# testpcb.net
KiCad netlist of a schematic drawn in EasyEDA Pro
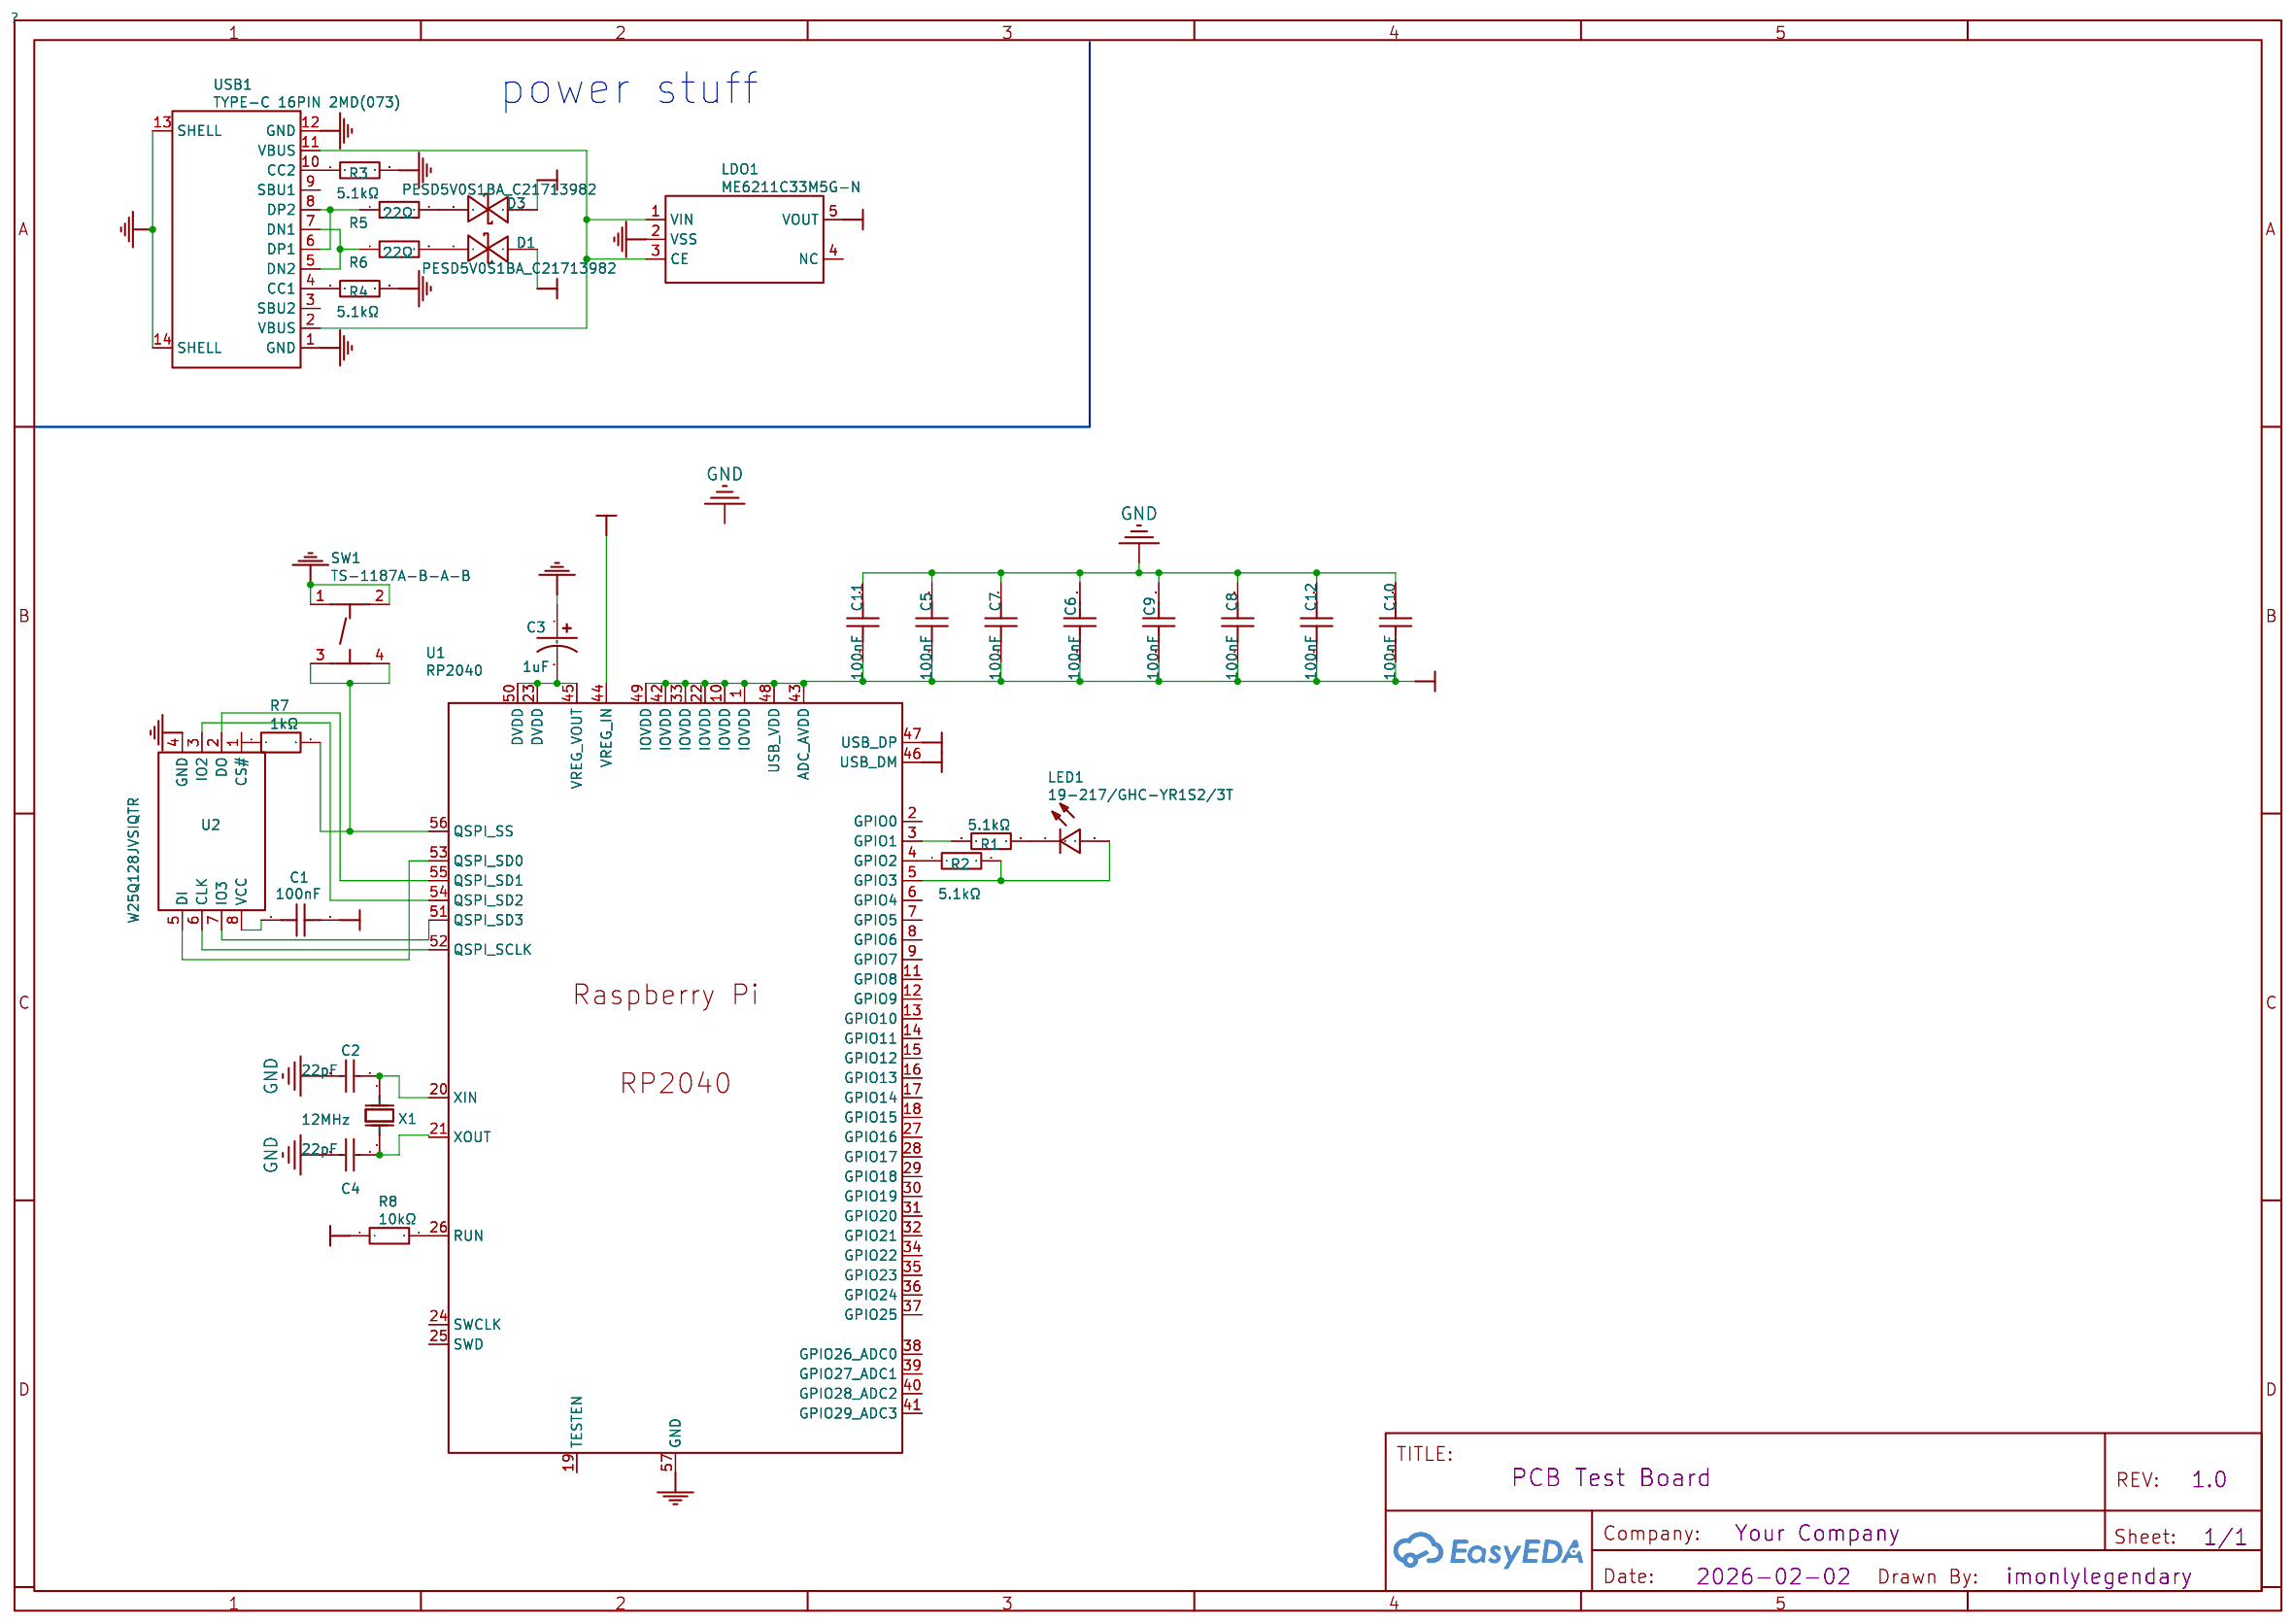
[diagram p0: schematic sheet]

(export (version "E")
  (design (tool "Eeschema 10.0.6"))
  (components
    (comp (ref "C1")
      (value "100nF")
      (footprint "easyedapro:C0402")
      (fields
        (field (name "Manufacturer Part") "CL05B104KB54PNC")
        (field (name "Manufacturer") "SAMSUNG(三星)")
        (field (name "Contributor") "LCSC")
      )
      (libsource (lib "") (part "100nF_1"))
    )
    (comp (ref "C2")
      (value "22pF")
      (footprint "easyedapro:C0603")
      (fields
        (field (name "Manufacturer Part") "CL10C220JB8NNNC")
        (field (name "Manufacturer") "SAMSUNG(三星)")
      )
      (libsource (lib "easyedapro") (part "22pF"))
    )
    (comp (ref "C3")
      (value "1uF")
      (footprint "easyedapro:CAP-TH_BD5.0-P2.00-D0.5-FD-1")
      (fields
        (field (name "Manufacturer Part") "50YXF1MEFC5X11")
        (field (name "Manufacturer") "rubycon(红宝石)")
        (field (name "Contributor") "lcsc")
      )
      (libsource (lib "easyedapro") (part "1uF"))
    )
    (comp (ref "C4")
      (value "22pF")
      (footprint "easyedapro:C0603")
      (fields
        (field (name "Manufacturer Part") "CL10C220JB8NNNC")
        (field (name "Manufacturer") "SAMSUNG(三星)")
      )
      (libsource (lib "easyedapro") (part "22pF"))
    )
    (comp (ref "C5")
      (value "100nF")
      (footprint "easyedapro:C0603")
      (fields
        (field (name "Manufacturer Part") "CC0603KRX7R9BB104")
        (field (name "Manufacturer") "YAGEO(国巨)")
      )
      (libsource (lib "easyedapro") (part "100nF"))
    )
    (comp (ref "C6")
      (value "100nF")
      (footprint "easyedapro:C0603")
      (fields
        (field (name "Manufacturer Part") "CC0603KRX7R9BB104")
        (field (name "Manufacturer") "YAGEO(国巨)")
      )
      (libsource (lib "easyedapro") (part "100nF"))
    )
    (comp (ref "C7")
      (value "100nF")
      (footprint "easyedapro:C0603")
      (fields
        (field (name "Manufacturer Part") "CC0603KRX7R9BB104")
        (field (name "Manufacturer") "YAGEO(国巨)")
      )
      (libsource (lib "easyedapro") (part "100nF"))
    )
    (comp (ref "C8")
      (value "100nF")
      (footprint "easyedapro:C0603")
      (fields
        (field (name "Manufacturer Part") "CC0603KRX7R9BB104")
        (field (name "Manufacturer") "YAGEO(国巨)")
      )
      (libsource (lib "easyedapro") (part "100nF"))
    )
    (comp (ref "C9")
      (value "100nF")
      (footprint "easyedapro:C0603")
      (fields
        (field (name "Manufacturer Part") "CC0603KRX7R9BB104")
        (field (name "Manufacturer") "YAGEO(国巨)")
      )
      (libsource (lib "easyedapro") (part "100nF"))
    )
    (comp (ref "C10")
      (value "100nF")
      (footprint "easyedapro:C0603")
      (fields
        (field (name "Manufacturer Part") "CC0603KRX7R9BB104")
        (field (name "Manufacturer") "YAGEO(国巨)")
      )
      (libsource (lib "easyedapro") (part "100nF"))
    )
    (comp (ref "C11")
      (value "100nF")
      (footprint "easyedapro:C0603")
      (fields
        (field (name "Manufacturer Part") "CC0603KRX7R9BB104")
        (field (name "Manufacturer") "YAGEO(国巨)")
      )
      (libsource (lib "easyedapro") (part "100nF"))
    )
    (comp (ref "C12")
      (value "100nF")
      (footprint "easyedapro:C0603")
      (fields
        (field (name "Manufacturer Part") "CC0603KRX7R9BB104")
        (field (name "Manufacturer") "YAGEO(国巨)")
      )
      (libsource (lib "easyedapro") (part "100nF"))
    )
    (comp (ref "D1")
      (value "PESD5V0S1BA_C21713982")
      (footprint "easyedapro:SOD-323_L1.7-W1.3-LS2.5-BI")
      (fields
        (field (name "Manufacturer Part") "PESD5V0S1BA")
        (field (name "Manufacturer") "GOODWORK(固得沃克)")
        (field (name "Contributor") "lcsc")
      )
      (libsource (lib "easyedapro") (part "PESD5V0S1BA_C21713982"))
    )
    (comp (ref "D3")
      (value "PESD5V0S1BA_C21713982")
      (footprint "easyedapro:SOD-323_L1.7-W1.3-LS2.5-BI")
      (fields
        (field (name "Manufacturer Part") "PESD5V0S1BA")
        (field (name "Manufacturer") "GOODWORK(固得沃克)")
        (field (name "Contributor") "lcsc")
      )
      (libsource (lib "easyedapro") (part "PESD5V0S1BA_C21713982"))
    )
    (comp (ref "LDO1")
      (value "ME6211C33M5G-N")
      (footprint "easyedapro:SOT-23-5_L3.0-W1.7-P0.95-LS2.8-BL")
      (fields (field (name "Manufacturer") "MICRONE(南京微盟)"))
      (libsource (lib "easyedapro") (part "ME6211C33M5G-N"))
    )
    (comp (ref "LED1")
      (value "19-217/GHC-YR1S2/3T")
      (footprint "easyedapro:LED0603-RD")
      (fields (field (name "Manufacturer") "EVERLIGHT(亿光)"))
      (libsource (lib "easyedapro") (part "19-217/GHC-YR1S2/3T"))
    )
    (comp (ref "R1")
      (value "5.1kΩ")
      (footprint "easyedapro:R0603")
      (fields
        (field (name "Manufacturer Part") "0603WAF5101T5E")
        (field (name "Manufacturer") "UNI-ROYAL(厚声)")
      )
      (libsource (lib "easyedapro") (part "5.1kΩ"))
    )
    (comp (ref "R2")
      (value "5.1kΩ")
      (footprint "easyedapro:R0603")
      (fields
        (field (name "Manufacturer Part") "0603WAF5101T5E")
        (field (name "Manufacturer") "UNI-ROYAL(厚声)")
      )
      (libsource (lib "easyedapro") (part "5.1kΩ"))
    )
    (comp (ref "R3")
      (value "5.1kΩ")
      (footprint "easyedapro:R0603")
      (fields
        (field (name "Manufacturer Part") "0603WAF5101T5E")
        (field (name "Manufacturer") "UNI-ROYAL(厚声)")
      )
      (libsource (lib "easyedapro") (part "5.1kΩ"))
    )
    (comp (ref "R4")
      (value "5.1kΩ")
      (footprint "easyedapro:R0603")
      (fields
        (field (name "Manufacturer Part") "0603WAF5101T5E")
        (field (name "Manufacturer") "UNI-ROYAL(厚声)")
      )
      (libsource (lib "easyedapro") (part "5.1kΩ"))
    )
    (comp (ref "R5")
      (value "22Ω")
      (footprint "easyedapro:R0603")
      (fields
        (field (name "Manufacturer Part") "0603WAF220JT5E")
        (field (name "Manufacturer") "UNI-ROYAL(厚声)")
      )
      (libsource (lib "easyedapro") (part "22Ω"))
    )
    (comp (ref "R6")
      (value "22Ω")
      (footprint "easyedapro:R0603")
      (fields
        (field (name "Manufacturer Part") "0603WAF220JT5E")
        (field (name "Manufacturer") "UNI-ROYAL(厚声)")
      )
      (libsource (lib "easyedapro") (part "22Ω"))
    )
    (comp (ref "R7")
      (value "1kΩ")
      (footprint "easyedapro:R0603")
      (fields
        (field (name "Manufacturer Part") "FRC0603F1001TS")
        (field (name "Manufacturer") "FOJAN(富捷)")
        (field (name "Contributor") "lcsc")
      )
      (libsource (lib "easyedapro") (part "1kΩ"))
    )
    (comp (ref "R8")
      (value "10kΩ")
      (footprint "easyedapro:R0603")
      (fields
        (field (name "Manufacturer Part") "0603WAF1002T5E")
        (field (name "Manufacturer") "UNI-ROYAL(厚声)")
      )
      (libsource (lib "easyedapro") (part "10kΩ"))
    )
    (comp (ref "SW1")
      (value "TS-1187A-B-A-B")
      (footprint "easyedapro:SW-SMD_4P-L5.1-W5.1-P3.70-LS6.5-TL_H1.5")
      (fields (field (name "Manufacturer") "XKB Connection(中国星坤)") (field (name "Contributor") "LCSC"))
      (libsource (lib "easyedapro") (part "TS-1187A-B-A-B"))
    )
    (comp (ref "U1")
      (value "RP2040")
      (footprint "easyedapro:LQFN-56_L7.0-W7.0-P0.4-EP")
      (fields (field (name "Manufacturer") "Raspberry Pi(树莓派)") (field (name "Contributor") "LCSC"))
      (libsource (lib "easyedapro") (part "RP2040"))
    )
    (comp (ref "U2")
      (value "W25Q128JVSIQTR")
      (footprint "easyedapro:SOIC-8_L5.3-W5.3-P1.27-LS8.0-BL")
      (fields (field (name "Manufacturer Part") "W25Q128JVSIQ") (field (name "Manufacturer") "Winbond(华邦)"))
      (libsource (lib "easyedapro") (part "W25Q128JVSIQTR"))
    )
    (comp (ref "USB1")
      (value "TYPE-C 16PIN 2MD(073)")
      (footprint "easyedapro:USB-C-SMD_TYPE-C-6PIN-2MD-073")
      (fields (field (name "Manufacturer") "SHOU HAN(首韩)") (field (name "Contributor") "LCSC"))
      (libsource (lib "easyedapro") (part "TYPE-C 16PIN 2MD(073)"))
    )
    (comp (ref "X1")
      (value "12MHz")
      (footprint "easyedapro:HC-49US_L11.5-W4.5-P4.88")
      (fields (field (name "Manufacturer Part") "X49SD12MSD2SC") (field (name "Manufacturer") "YXC(扬兴晶振)"))
      (libsource (lib "easyedapro") (part "12MHz"))
    )
  )
  (nets
    (net (code "1") (name "3.3V") (class "Default")
      (node (ref "C1") (pin "2") (pinfunction "2_2") (pintype "unspecified"))
      (node (ref "C10") (pin "1") (pinfunction "1_1") (pintype "unspecified"))
      (node (ref "C11") (pin "1") (pinfunction "1_1") (pintype "unspecified"))
      (node (ref "C12") (pin "1") (pinfunction "1_1") (pintype "unspecified"))
      (node (ref "C5") (pin "1") (pinfunction "1_1") (pintype "unspecified"))
      (node (ref "C6") (pin "1") (pinfunction "1_1") (pintype "unspecified"))
      (node (ref "C7") (pin "1") (pinfunction "1_1") (pintype "unspecified"))
      (node (ref "C8") (pin "1") (pinfunction "1_1") (pintype "unspecified"))
      (node (ref "C9") (pin "1") (pinfunction "1_1") (pintype "unspecified"))
      (node (ref "LDO1") (pin "5") (pinfunction "VOUT_5") (pintype "unspecified"))
      (node (ref "R8") (pin "1") (pinfunction "1_1") (pintype "input"))
      (node (ref "U1") (pin "44") (pinfunction "VREG_IN_44") (pintype "bidirectional"))
    )
    (net (code "2") (name "D+") (class "Default")
      (node (ref "D3") (pin "2") (pinfunction "K_2") (pintype "unspecified"))
      (node (ref "U1") (pin "47") (pinfunction "USB_DP_47") (pintype "bidirectional"))
    )
    (net (code "3") (name "D-") (class "Default")
      (node (ref "D1") (pin "2") (pinfunction "K_2") (pintype "unspecified"))
      (node (ref "U1") (pin "46") (pinfunction "USB_DM_46") (pintype "bidirectional"))
    )
    (net (code "4") (name "GND") (class "Default")
      (node (ref "C10") (pin "2") (pinfunction "2_2") (pintype "unspecified"))
      (node (ref "C11") (pin "2") (pinfunction "2_2") (pintype "unspecified"))
      (node (ref "C12") (pin "2") (pinfunction "2_2") (pintype "unspecified"))
      (node (ref "C2") (pin "1") (pinfunction "1_1") (pintype "input"))
      (node (ref "C3") (pin "1") (pinfunction "1_1") (pintype "unspecified"))
      (node (ref "C4") (pin "1") (pinfunction "1_1") (pintype "input"))
      (node (ref "C5") (pin "2") (pinfunction "2_2") (pintype "unspecified"))
      (node (ref "C6") (pin "2") (pinfunction "2_2") (pintype "unspecified"))
      (node (ref "C7") (pin "2") (pinfunction "2_2") (pintype "unspecified"))
      (node (ref "C8") (pin "2") (pinfunction "2_2") (pintype "unspecified"))
      (node (ref "C9") (pin "2") (pinfunction "2_2") (pintype "unspecified"))
      (node (ref "LDO1") (pin "2") (pinfunction "VSS_2") (pintype "unspecified"))
      (node (ref "R3") (pin "2") (pinfunction "2_2") (pintype "input"))
      (node (ref "R4") (pin "2") (pinfunction "2_2") (pintype "input"))
      (node (ref "SW1") (pin "1") (pinfunction "A_1") (pintype "unspecified"))
      (node (ref "SW1") (pin "2") (pinfunction "B_2") (pintype "unspecified"))
      (node (ref "U1") (pin "57") (pinfunction "GND_57") (pintype "bidirectional"))
      (node (ref "U2") (pin "4") (pinfunction "GND_4") (pintype "unspecified"))
      (node (ref "USB1") (pin "1") (pinfunction "GND_1") (pintype "unspecified"))
      (node (ref "USB1") (pin "12") (pinfunction "GND_12") (pintype "unspecified"))
      (node (ref "USB1") (pin "13") (pinfunction "SHELL_13") (pintype "unspecified"))
      (node (ref "USB1") (pin "14") (pinfunction "SHELL_14") (pintype "unspecified"))
    )
    (net (code "5") (name "Net-(D1-A)") (class "Default")
      (node (ref "D1") (pin "1") (pinfunction "A_1") (pintype "unspecified"))
      (node (ref "R6") (pin "2") (pinfunction "2_2") (pintype "input"))
    )
    (net (code "6") (name "Net-(D3-A)") (class "Default")
      (node (ref "D3") (pin "1") (pinfunction "A_1") (pintype "unspecified"))
      (node (ref "R5") (pin "2") (pinfunction "2_2") (pintype "input"))
    )
    (net (code "7") (name "Net-(LDO1-CE)") (class "Default")
      (node (ref "LDO1") (pin "1") (pinfunction "VIN_1") (pintype "unspecified"))
      (node (ref "LDO1") (pin "3") (pinfunction "CE_3") (pintype "unspecified"))
      (node (ref "USB1") (pin "11") (pinfunction "VBUS_11") (pintype "unspecified"))
      (node (ref "USB1") (pin "2") (pinfunction "VBUS_2") (pintype "unspecified"))
    )
    (net (code "8") (name "Net-(LED1-A)") (class "Default")
      (node (ref "LED1") (pin "2") (pinfunction "A_2") (pintype "input"))
      (node (ref "R2") (pin "2") (pinfunction "2_2") (pintype "input"))
      (node (ref "U1") (pin "5") (pinfunction "GPIO3_5") (pintype "bidirectional"))
    )
    (net (code "9") (name "Net-(LED1-C)") (class "Default")
      (node (ref "LED1") (pin "1") (pinfunction "C_1") (pintype "input"))
      (node (ref "R1") (pin "2") (pinfunction "2_2") (pintype "input"))
    )
    (net (code "10") (name "Net-(SW1-C)") (class "Default")
      (node (ref "R7") (pin "2") (pinfunction "2_2") (pintype "unspecified"))
      (node (ref "SW1") (pin "3") (pinfunction "C_3") (pintype "unspecified"))
      (node (ref "SW1") (pin "4") (pinfunction "D_4") (pintype "unspecified"))
      (node (ref "U1") (pin "56") (pinfunction "QSPI_SS_56") (pintype "bidirectional"))
    )
    (net (code "11") (name "Net-(U1-ADC_AVDD)") (class "Default")
      (node (ref "U1") (pin "1") (pinfunction "IOVDD_1") (pintype "bidirectional"))
      (node (ref "U1") (pin "10") (pinfunction "IOVDD_10") (pintype "bidirectional"))
      (node (ref "U1") (pin "22") (pinfunction "IOVDD_22") (pintype "bidirectional"))
      (node (ref "U1") (pin "33") (pinfunction "IOVDD_33") (pintype "bidirectional"))
      (node (ref "U1") (pin "42") (pinfunction "IOVDD_42") (pintype "bidirectional"))
      (node (ref "U1") (pin "43") (pinfunction "ADC_AVDD_43") (pintype "bidirectional"))
      (node (ref "U1") (pin "48") (pinfunction "USB_VDD_48") (pintype "bidirectional"))
      (node (ref "U1") (pin "49") (pinfunction "IOVDD_49") (pintype "bidirectional"))
    )
    (net (code "12") (name "Net-(U1-GPIO1)") (class "Default")
      (node (ref "R1") (pin "1") (pinfunction "1_1") (pintype "input"))
      (node (ref "U1") (pin "3") (pinfunction "GPIO1_3") (pintype "bidirectional"))
    )
    (net (code "13") (name "Net-(U1-GPIO2)") (class "Default")
      (node (ref "R2") (pin "1") (pinfunction "1_1") (pintype "input"))
      (node (ref "U1") (pin "4") (pinfunction "GPIO2_4") (pintype "bidirectional"))
    )
    (net (code "14") (name "Net-(U1-QSPI_SCLK)") (class "Default")
      (node (ref "U1") (pin "52") (pinfunction "QSPI_SCLK_52") (pintype "output"))
      (node (ref "U2") (pin "6") (pinfunction "CLK_6") (pintype "unspecified"))
    )
    (net (code "15") (name "Net-(U1-QSPI_SD0)") (class "Default")
      (node (ref "U1") (pin "53") (pinfunction "QSPI_SD0_53") (pintype "bidirectional"))
      (node (ref "U2") (pin "5") (pinfunction "DI_5") (pintype "unspecified"))
    )
    (net (code "16") (name "Net-(U1-QSPI_SD1)") (class "Default")
      (node (ref "U1") (pin "55") (pinfunction "QSPI_SD1_55") (pintype "bidirectional"))
      (node (ref "U2") (pin "2") (pinfunction "DO_2") (pintype "unspecified"))
    )
    (net (code "17") (name "Net-(U1-QSPI_SD2)") (class "Default")
      (node (ref "U1") (pin "54") (pinfunction "QSPI_SD2_54") (pintype "bidirectional"))
      (node (ref "U2") (pin "3") (pinfunction "IO2_3") (pintype "unspecified"))
    )
    (net (code "18") (name "Net-(U1-QSPI_SD3)") (class "Default")
      (node (ref "U1") (pin "51") (pinfunction "QSPI_SD3_51") (pintype "bidirectional"))
      (node (ref "U2") (pin "7") (pinfunction "IO3_7") (pintype "unspecified"))
    )
    (net (code "19") (name "Net-(U1-RUN)") (class "Default")
      (node (ref "R8") (pin "2") (pinfunction "2_2") (pintype "input"))
      (node (ref "U1") (pin "26") (pinfunction "RUN_26") (pintype "input"))
    )
    (net (code "20") (name "Net-(U1-VREG_VOUT)") (class "Default")
      (node (ref "C3") (pin "2") (pinfunction "2_2") (pintype "unspecified"))
      (node (ref "U1") (pin "23") (pinfunction "DVDD_23") (pintype "bidirectional"))
      (node (ref "U1") (pin "45") (pinfunction "VREG_VOUT_45") (pintype "bidirectional"))
      (node (ref "U1") (pin "50") (pinfunction "DVDD_50") (pintype "bidirectional"))
    )
    (net (code "21") (name "Net-(U1-XIN)") (class "Default")
      (node (ref "C2") (pin "2") (pinfunction "2_2") (pintype "input"))
      (node (ref "U1") (pin "20") (pinfunction "XIN_20") (pintype "input"))
      (node (ref "X1") (pin "1") (pinfunction "OSC1_1") (pintype "input"))
    )
    (net (code "22") (name "Net-(U1-XOUT)") (class "Default")
      (node (ref "C4") (pin "2") (pinfunction "2_2") (pintype "input"))
      (node (ref "U1") (pin "21") (pinfunction "XOUT_21") (pintype "unspecified"))
      (node (ref "X1") (pin "2") (pinfunction "OSC2_2") (pintype "input"))
    )
    (net (code "23") (name "Net-(U2-CS#)") (class "Default")
      (node (ref "R7") (pin "1") (pinfunction "1_1") (pintype "unspecified"))
      (node (ref "U2") (pin "1") (pinfunction "CS#_1") (pintype "unspecified"))
    )
    (net (code "24") (name "Net-(U2-VCC)") (class "Default")
      (node (ref "C1") (pin "1") (pinfunction "1_1") (pintype "unspecified"))
      (node (ref "U2") (pin "8") (pinfunction "VCC_8") (pintype "unspecified"))
    )
    (net (code "25") (name "Net-(USB1-CC1)") (class "Default")
      (node (ref "R4") (pin "1") (pinfunction "1_1") (pintype "input"))
      (node (ref "USB1") (pin "4") (pinfunction "CC1_4") (pintype "unspecified"))
    )
    (net (code "26") (name "Net-(USB1-CC2)") (class "Default")
      (node (ref "R3") (pin "1") (pinfunction "1_1") (pintype "input"))
      (node (ref "USB1") (pin "10") (pinfunction "CC2_10") (pintype "unspecified"))
    )
    (net (code "27") (name "Net-(USB1-DN1)") (class "Default")
      (node (ref "R6") (pin "1") (pinfunction "1_1") (pintype "input"))
      (node (ref "USB1") (pin "5") (pinfunction "DN2_5") (pintype "unspecified"))
      (node (ref "USB1") (pin "7") (pinfunction "DN1_7") (pintype "unspecified"))
    )
    (net (code "28") (name "Net-(USB1-DP1)") (class "Default")
      (node (ref "R5") (pin "1") (pinfunction "1_1") (pintype "input"))
      (node (ref "USB1") (pin "6") (pinfunction "DP1_6") (pintype "unspecified"))
      (node (ref "USB1") (pin "8") (pinfunction "DP2_8") (pintype "unspecified"))
    )
    (net (code "29") (name "unconnected-(LDO1-NC-Pad4)") (class "Default")
      (node (ref "LDO1") (pin "4") (pinfunction "NC_4") (pintype "unspecified"))
    )
    (net (code "30") (name "unconnected-(U1-GPIO0-Pad2)") (class "Default")
      (node (ref "U1") (pin "2") (pinfunction "GPIO0_2") (pintype "bidirectional"))
    )
    (net (code "31") (name "unconnected-(U1-GPIO4-Pad6)") (class "Default")
      (node (ref "U1") (pin "6") (pinfunction "GPIO4_6") (pintype "bidirectional"))
    )
    (net (code "32") (name "unconnected-(U1-GPIO5-Pad7)") (class "Default")
      (node (ref "U1") (pin "7") (pinfunction "GPIO5_7") (pintype "bidirectional"))
    )
    (net (code "33") (name "unconnected-(U1-GPIO6-Pad8)") (class "Default")
      (node (ref "U1") (pin "8") (pinfunction "GPIO6_8") (pintype "bidirectional"))
    )
    (net (code "34") (name "unconnected-(U1-GPIO7-Pad9)") (class "Default")
      (node (ref "U1") (pin "9") (pinfunction "GPIO7_9") (pintype "bidirectional"))
    )
    (net (code "35") (name "unconnected-(U1-GPIO8-Pad11)") (class "Default")
      (node (ref "U1") (pin "11") (pinfunction "GPIO8_11") (pintype "bidirectional"))
    )
    (net (code "36") (name "unconnected-(U1-GPIO9-Pad12)") (class "Default")
      (node (ref "U1") (pin "12") (pinfunction "GPIO9_12") (pintype "bidirectional"))
    )
    (net (code "37") (name "unconnected-(U1-GPIO10-Pad13)") (class "Default")
      (node (ref "U1") (pin "13") (pinfunction "GPIO10_13") (pintype "bidirectional"))
    )
    (net (code "38") (name "unconnected-(U1-GPIO11-Pad14)") (class "Default")
      (node (ref "U1") (pin "14") (pinfunction "GPIO11_14") (pintype "bidirectional"))
    )
    (net (code "39") (name "unconnected-(U1-GPIO12-Pad15)") (class "Default")
      (node (ref "U1") (pin "15") (pinfunction "GPIO12_15") (pintype "bidirectional"))
    )
    (net (code "40") (name "unconnected-(U1-GPIO13-Pad16)") (class "Default")
      (node (ref "U1") (pin "16") (pinfunction "GPIO13_16") (pintype "bidirectional"))
    )
    (net (code "41") (name "unconnected-(U1-GPIO14-Pad17)") (class "Default")
      (node (ref "U1") (pin "17") (pinfunction "GPIO14_17") (pintype "bidirectional"))
    )
    (net (code "42") (name "unconnected-(U1-GPIO15-Pad18)") (class "Default")
      (node (ref "U1") (pin "18") (pinfunction "GPIO15_18") (pintype "bidirectional"))
    )
    (net (code "43") (name "unconnected-(U1-GPIO16-Pad27)") (class "Default")
      (node (ref "U1") (pin "27") (pinfunction "GPIO16_27") (pintype "bidirectional"))
    )
    (net (code "44") (name "unconnected-(U1-GPIO17-Pad28)") (class "Default")
      (node (ref "U1") (pin "28") (pinfunction "GPIO17_28") (pintype "bidirectional"))
    )
    (net (code "45") (name "unconnected-(U1-GPIO18-Pad29)") (class "Default")
      (node (ref "U1") (pin "29") (pinfunction "GPIO18_29") (pintype "bidirectional"))
    )
    (net (code "46") (name "unconnected-(U1-GPIO19-Pad30)") (class "Default")
      (node (ref "U1") (pin "30") (pinfunction "GPIO19_30") (pintype "bidirectional"))
    )
    (net (code "47") (name "unconnected-(U1-GPIO20-Pad31)") (class "Default")
      (node (ref "U1") (pin "31") (pinfunction "GPIO20_31") (pintype "bidirectional"))
    )
    (net (code "48") (name "unconnected-(U1-GPIO21-Pad32)") (class "Default")
      (node (ref "U1") (pin "32") (pinfunction "GPIO21_32") (pintype "bidirectional"))
    )
    (net (code "49") (name "unconnected-(U1-GPIO22-Pad34)") (class "Default")
      (node (ref "U1") (pin "34") (pinfunction "GPIO22_34") (pintype "bidirectional"))
    )
    (net (code "50") (name "unconnected-(U1-GPIO23-Pad35)") (class "Default")
      (node (ref "U1") (pin "35") (pinfunction "GPIO23_35") (pintype "bidirectional"))
    )
    (net (code "51") (name "unconnected-(U1-GPIO24-Pad36)") (class "Default")
      (node (ref "U1") (pin "36") (pinfunction "GPIO24_36") (pintype "bidirectional"))
    )
    (net (code "52") (name "unconnected-(U1-GPIO25-Pad37)") (class "Default")
      (node (ref "U1") (pin "37") (pinfunction "GPIO25_37") (pintype "bidirectional"))
    )
    (net (code "53") (name "unconnected-(U1-GPIO26_ADC0-Pad38)") (class "Default")
      (node (ref "U1") (pin "38") (pinfunction "GPIO26_ADC0_38") (pintype "bidirectional"))
    )
    (net (code "54") (name "unconnected-(U1-GPIO27_ADC1-Pad39)") (class "Default")
      (node (ref "U1") (pin "39") (pinfunction "GPIO27_ADC1_39") (pintype "bidirectional"))
    )
    (net (code "55") (name "unconnected-(U1-GPIO28_ADC2-Pad40)") (class "Default")
      (node (ref "U1") (pin "40") (pinfunction "GPIO28_ADC2_40") (pintype "bidirectional"))
    )
    (net (code "56") (name "unconnected-(U1-GPIO29_ADC3-Pad41)") (class "Default")
      (node (ref "U1") (pin "41") (pinfunction "GPIO29_ADC3_41") (pintype "bidirectional"))
    )
    (net (code "57") (name "unconnected-(U1-SWCLK-Pad24)") (class "Default")
      (node (ref "U1") (pin "24") (pinfunction "SWCLK_24") (pintype "output"))
    )
    (net (code "58") (name "unconnected-(U1-SWD-Pad25)") (class "Default")
      (node (ref "U1") (pin "25") (pinfunction "SWD_25") (pintype "bidirectional"))
    )
    (net (code "59") (name "unconnected-(U1-TESTEN-Pad19)") (class "Default")
      (node (ref "U1") (pin "19") (pinfunction "TESTEN_19") (pintype "unspecified"))
    )
    (net (code "60") (name "unconnected-(USB1-SBU1-Pad9)") (class "Default")
      (node (ref "USB1") (pin "9") (pinfunction "SBU1_9") (pintype "unspecified"))
    )
    (net (code "61") (name "unconnected-(USB1-SBU2-Pad3)") (class "Default")
      (node (ref "USB1") (pin "3") (pinfunction "SBU2_3") (pintype "unspecified"))
    )
  )
)
